# tx_btns.net
KiCad netlist of a schematic drawn in EAGLE
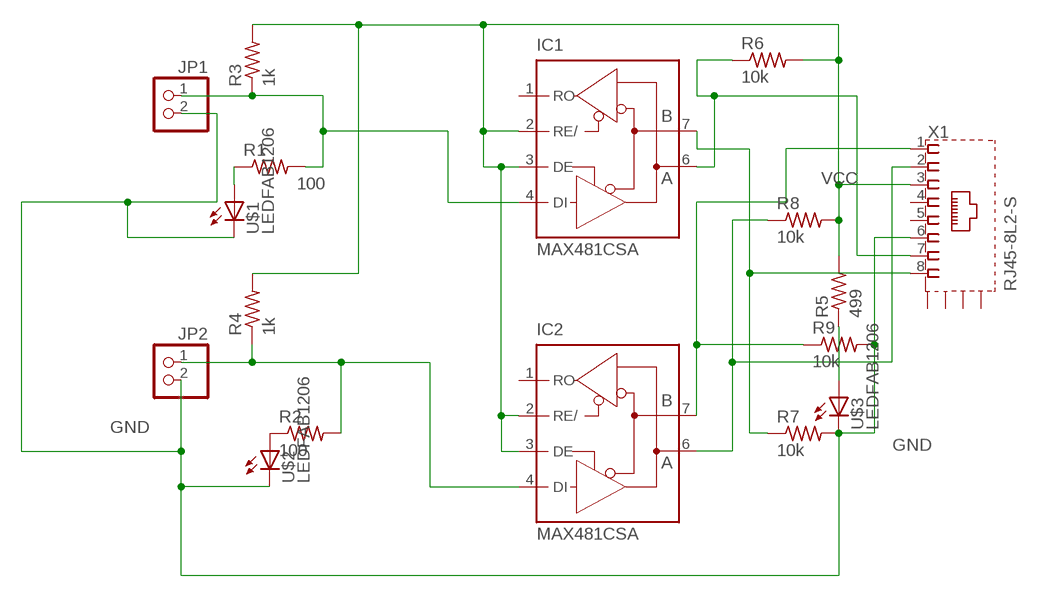
[diagram p0: schematic, sheet 1]

(export (version "E")
  (design (tool "Eeschema 10.0.6"))
  (components
    (comp (ref "IC1")
      (value "MAX481CSA")
      (footprint "eagle-import:SO08")
      (fields (field (name "MF") "MAXIM"))
      (libsource (lib "eagle-import") (part "MAX481CSA"))
    )
    (comp (ref "IC2")
      (value "MAX481CSA")
      (footprint "eagle-import:SO08")
      (fields (field (name "MF") "MAXIM"))
      (libsource (lib "eagle-import") (part "MAX481CSA"))
    )
    (comp (ref "JP1")
      (value "PINHD-1X2/90")
      (footprint "eagle-import:1X02_90")
      (libsource (lib "eagle-import") (part "PINHD-1X2/90"))
    )
    (comp (ref "JP2")
      (value "PINHD-1X2/90")
      (footprint "eagle-import:1X02_90")
      (libsource (lib "eagle-import") (part "PINHD-1X2/90"))
    )
    (comp (ref "R1")
      (value "100")
      (footprint "eagle-import:R1206FAB")
      (libsource (lib "eagle-import") (part "RES-US1206FAB"))
    )
    (comp (ref "R2")
      (value "100")
      (footprint "eagle-import:R1206FAB")
      (libsource (lib "eagle-import") (part "RES-US1206FAB"))
    )
    (comp (ref "R3")
      (value "1k")
      (footprint "eagle-import:R1206FAB")
      (libsource (lib "eagle-import") (part "RES-US1206FAB"))
    )
    (comp (ref "R4")
      (value "1k")
      (footprint "eagle-import:R1206FAB")
      (libsource (lib "eagle-import") (part "RES-US1206FAB"))
    )
    (comp (ref "R5")
      (value "499")
      (footprint "eagle-import:R1206FAB")
      (libsource (lib "eagle-import") (part "RES-US1206FAB"))
    )
    (comp (ref "R6")
      (value "10k")
      (footprint "eagle-import:R1206FAB")
      (libsource (lib "eagle-import") (part "RES-US1206FAB"))
    )
    (comp (ref "R7")
      (value "10k")
      (footprint "eagle-import:R1206FAB")
      (libsource (lib "eagle-import") (part "RES-US1206FAB"))
    )
    (comp (ref "R8")
      (value "10k")
      (footprint "eagle-import:R1206FAB")
      (libsource (lib "eagle-import") (part "RES-US1206FAB"))
    )
    (comp (ref "R9")
      (value "10k")
      (footprint "eagle-import:R1206FAB")
      (libsource (lib "eagle-import") (part "RES-US1206FAB"))
    )
    (comp (ref "U$1")
      (value "LEDFAB1206")
      (footprint "eagle-import:LED1206FAB")
      (libsource (lib "eagle-import") (part "LEDFAB1206"))
    )
    (comp (ref "U$2")
      (value "LEDFAB1206")
      (footprint "eagle-import:LED1206FAB")
      (libsource (lib "eagle-import") (part "LEDFAB1206"))
    )
    (comp (ref "U$3")
      (value "LEDFAB1206")
      (footprint "eagle-import:LED1206FAB")
      (libsource (lib "eagle-import") (part "LEDFAB1206"))
    )
    (comp (ref "X1")
      (value "RJ45-8L2-S")
      (footprint "eagle-import:RJ45-SHIELD2")
      (fields (field (name "MF") "TYCO ELECTRONICS"))
      (libsource (lib "eagle-import") (part "RJ452-S-8L"))
    )
  )
  (nets
    (net (code "1") (name "/GND") (class "Default")
      (node (ref "JP1") (pin "2") (pinfunction "2_2") (pintype "passive"))
      (node (ref "JP2") (pin "2") (pinfunction "2_2") (pintype "passive"))
      (node (ref "R7") (pin "2") (pinfunction "2_2") (pintype "passive"))
      (node (ref "R9") (pin "2") (pinfunction "2_2") (pintype "passive"))
      (node (ref "U$1") (pin "2") (pinfunction "C_2") (pintype "passive"))
      (node (ref "U$2") (pin "2") (pinfunction "C_2") (pintype "passive"))
      (node (ref "U$3") (pin "2") (pinfunction "C_2") (pintype "passive"))
      (node (ref "X1") (pin "6") (pinfunction "6_6") (pintype "passive"))
    )
    (net (code "2") (name "/VCC") (class "Default")
      (node (ref "IC1") (pin "2") (pinfunction "RE/_2") (pintype "input"))
      (node (ref "IC1") (pin "3") (pinfunction "DE_3") (pintype "input"))
      (node (ref "IC2") (pin "2") (pinfunction "RE/_2") (pintype "input"))
      (node (ref "IC2") (pin "3") (pinfunction "DE_3") (pintype "input"))
      (node (ref "R3") (pin "2") (pinfunction "2_2") (pintype "passive"))
      (node (ref "R4") (pin "2") (pinfunction "2_2") (pintype "passive"))
      (node (ref "R5") (pin "2") (pinfunction "2_2") (pintype "passive"))
      (node (ref "R6") (pin "2") (pinfunction "2_2") (pintype "passive"))
      (node (ref "R8") (pin "2") (pinfunction "2_2") (pintype "passive"))
      (node (ref "X1") (pin "3") (pinfunction "3_3") (pintype "passive"))
    )
    (net (code "3") (name "Net-(IC1A-A)") (class "Default")
      (node (ref "IC1") (pin "6") (pinfunction "A_6") (pintype "passive"))
      (node (ref "R6") (pin "1") (pinfunction "1_1") (pintype "passive"))
      (node (ref "X1") (pin "7") (pinfunction "7_7") (pintype "passive"))
    )
    (net (code "4") (name "Net-(IC1A-B)") (class "Default")
      (node (ref "IC1") (pin "7") (pinfunction "B_7") (pintype "passive"))
      (node (ref "R7") (pin "1") (pinfunction "1_1") (pintype "passive"))
      (node (ref "X1") (pin "8") (pinfunction "8_8") (pintype "passive"))
    )
    (net (code "5") (name "Net-(IC1A-DI)") (class "Default")
      (node (ref "IC1") (pin "4") (pinfunction "DI_4") (pintype "input"))
      (node (ref "JP1") (pin "1") (pinfunction "1_1") (pintype "passive"))
      (node (ref "R1") (pin "2") (pinfunction "2_2") (pintype "passive"))
      (node (ref "R3") (pin "1") (pinfunction "1_1") (pintype "passive"))
    )
    (net (code "6") (name "Net-(IC2A-A)") (class "Default")
      (node (ref "IC2") (pin "6") (pinfunction "A_6") (pintype "passive"))
      (node (ref "R8") (pin "1") (pinfunction "1_1") (pintype "passive"))
      (node (ref "X1") (pin "2") (pinfunction "2_2") (pintype "passive"))
    )
    (net (code "7") (name "Net-(IC2A-B)") (class "Default")
      (node (ref "IC2") (pin "7") (pinfunction "B_7") (pintype "passive"))
      (node (ref "R9") (pin "1") (pinfunction "1_1") (pintype "passive"))
      (node (ref "X1") (pin "1") (pinfunction "1_1") (pintype "passive"))
    )
    (net (code "8") (name "Net-(IC2A-DI)") (class "Default")
      (node (ref "IC2") (pin "4") (pinfunction "DI_4") (pintype "input"))
      (node (ref "JP2") (pin "1") (pinfunction "1_1") (pintype "passive"))
      (node (ref "R2") (pin "2") (pinfunction "2_2") (pintype "passive"))
      (node (ref "R4") (pin "1") (pinfunction "1_1") (pintype "passive"))
    )
    (net (code "9") (name "Net-(U$1-A)") (class "Default")
      (node (ref "R1") (pin "1") (pinfunction "1_1") (pintype "passive"))
      (node (ref "U$1") (pin "1") (pinfunction "A_1") (pintype "passive"))
    )
    (net (code "10") (name "Net-(U$2-A)") (class "Default")
      (node (ref "R2") (pin "1") (pinfunction "1_1") (pintype "passive"))
      (node (ref "U$2") (pin "1") (pinfunction "A_1") (pintype "passive"))
    )
    (net (code "11") (name "Net-(U$3-A)") (class "Default")
      (node (ref "R5") (pin "1") (pinfunction "1_1") (pintype "passive"))
      (node (ref "U$3") (pin "1") (pinfunction "A_1") (pintype "passive"))
    )
    (net (code "12") (name "unconnected-(IC1A-RO-Pad1)") (class "Default")
      (node (ref "IC1") (pin "1") (pinfunction "RO_1") (pintype "output"))
    )
    (net (code "13") (name "unconnected-(IC2A-RO-Pad1)") (class "Default")
      (node (ref "IC2") (pin "1") (pinfunction "RO_1") (pintype "output"))
    )
    (net (code "14") (name "unconnected-(X1-Pad4)") (class "Default")
      (node (ref "X1") (pin "4") (pinfunction "4_4") (pintype "passive"))
    )
    (net (code "15") (name "unconnected-(X1-Pad5)") (class "Default")
      (node (ref "X1") (pin "5") (pinfunction "5_5") (pintype "passive"))
    )
    (net (code "16") (name "unconnected-(X1-S-PadS1)") (class "Default")
      (node (ref "X1") (pin "S1") (pinfunction "S_S1") (pintype "passive"))
    )
    (net (code "17") (name "unconnected-(X1-S-PadS2)") (class "Default")
      (node (ref "X1") (pin "S2") (pinfunction "S_S2") (pintype "passive"))
    )
    (net (code "18") (name "unconnected-(X1-S-PadS3)") (class "Default")
      (node (ref "X1") (pin "S3") (pinfunction "S_S3") (pintype "passive"))
    )
    (net (code "19") (name "unconnected-(X1-S-PadS4)") (class "Default")
      (node (ref "X1") (pin "S4") (pinfunction "S_S4") (pintype "passive"))
    )
  )
)
